# HMC5883L_Breakout-v11.net
KiCad netlist of a schematic drawn in EAGLE
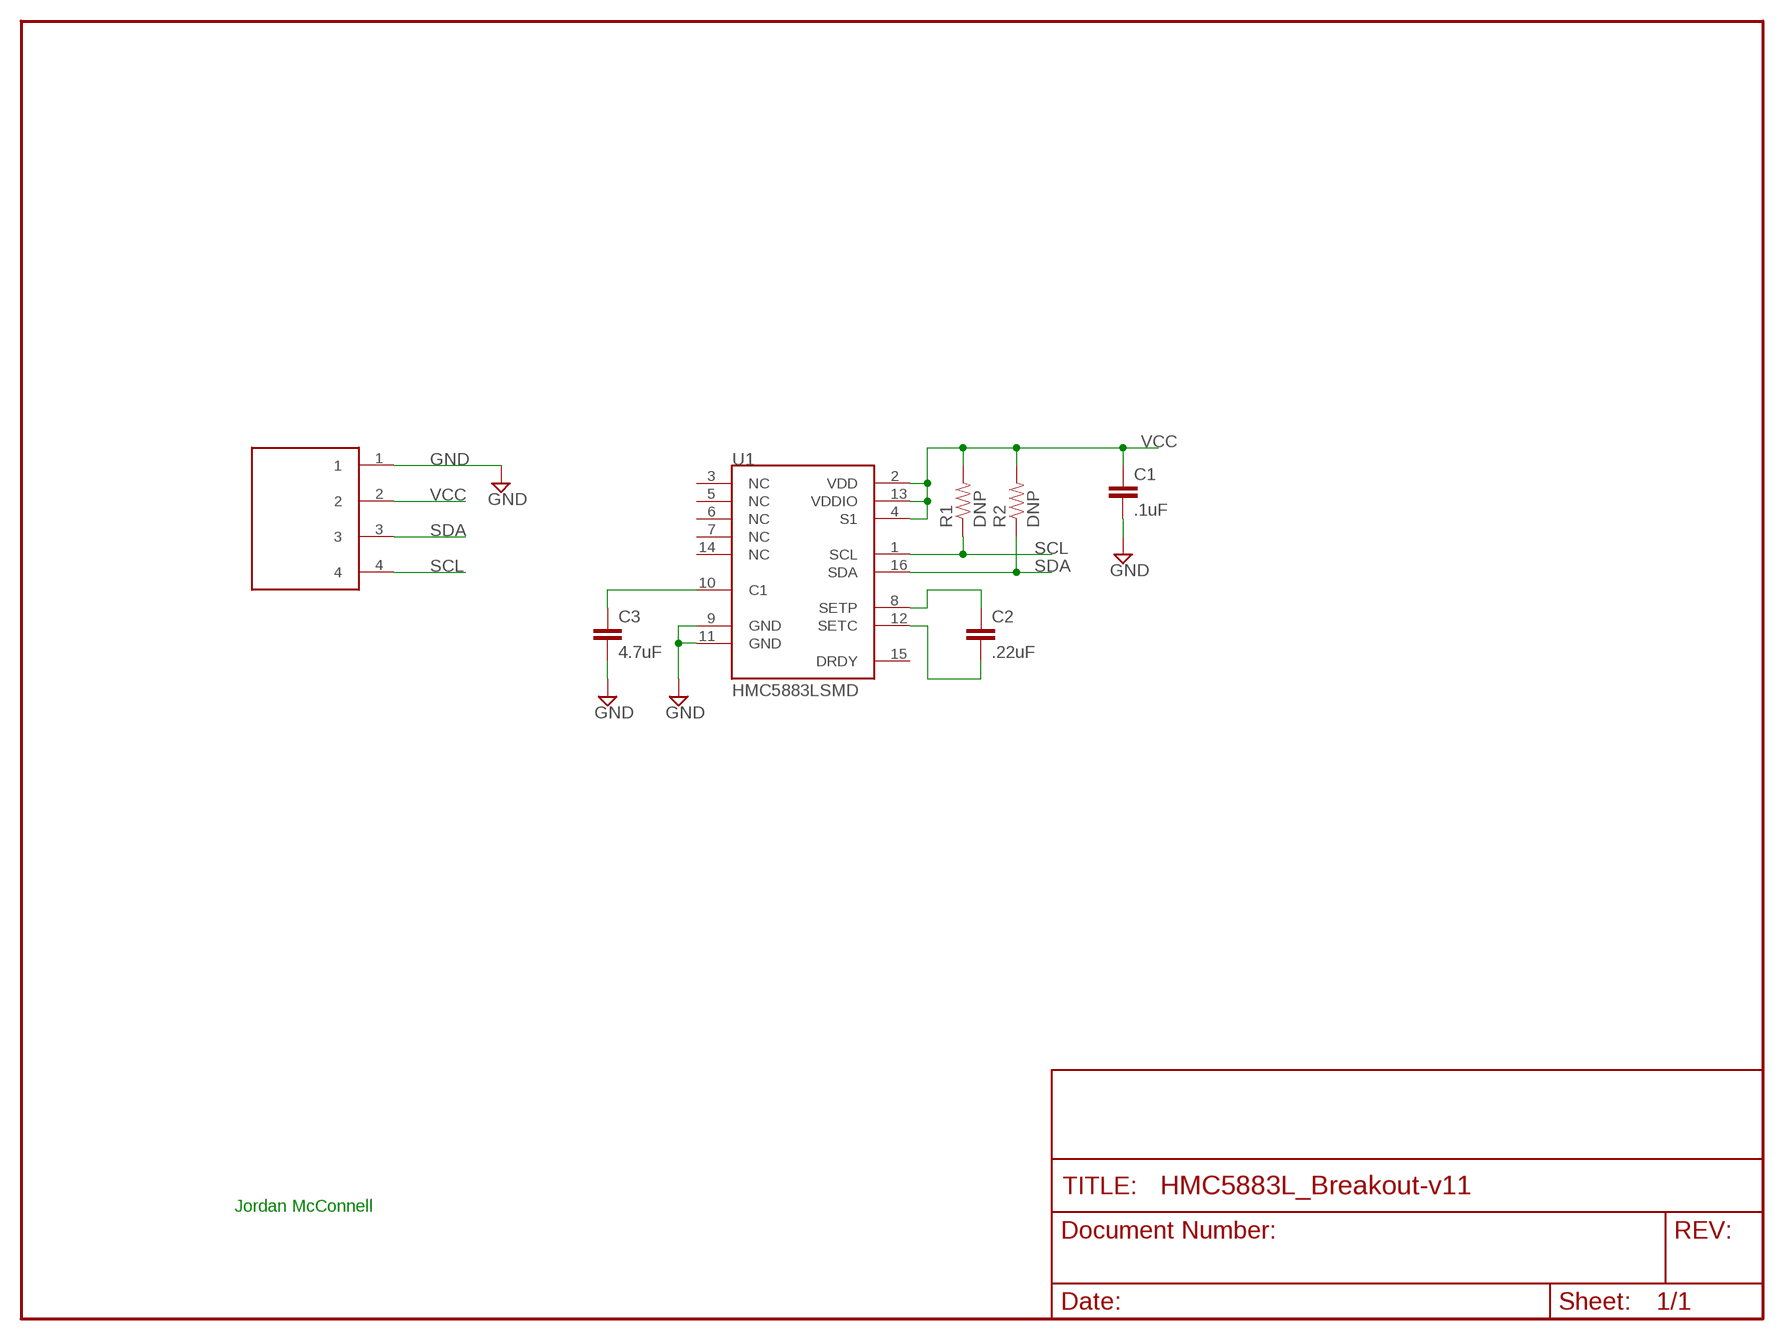
[diagram p0: schematic, sheet 1]

(export (version "E")
  (design (tool "Eeschema 10.0.6"))
  (components
    (comp (ref "C1")
      (value ".1uF")
      (footprint "eagle-import:0402-CAP")
      (libsource (lib "eagle-import") (part "CAP0402-CAP"))
    )
    (comp (ref "C2")
      (value ".22uF")
      (footprint "eagle-import:0402-CAP")
      (libsource (lib "eagle-import") (part "CAP0402-CAP"))
    )
    (comp (ref "C3")
      (value "4.7uF")
      (footprint "eagle-import:0402-CAP")
      (libsource (lib "eagle-import") (part "CAP0402-CAP"))
    )
    (comp (ref "JP1")
      (value "M80-879")
      (footprint "eagle-import:M80-879")
      (libsource (lib "eagle-import") (part "M80-879"))
    )
    (comp (ref "R1")
      (value "DNP")
      (footprint "eagle-import:0402-RES")
      (libsource (lib "eagle-import") (part "RESISTOR0402-RES"))
    )
    (comp (ref "R2")
      (value "DNP")
      (footprint "eagle-import:0402-RES")
      (libsource (lib "eagle-import") (part "RESISTOR0402-RES"))
    )
    (comp (ref "U1")
      (value "HMC5883LSMD")
      (footprint "eagle-import:16LPCC")
      (libsource (lib "eagle-import") (part "HMC5883LSMD"))
    )
  )
  (nets
    (net (code "1") (name "/SCL") (class "Default")
      (node (ref "JP1") (pin "4") (pinfunction "4_4") (pintype "bidirectional"))
      (node (ref "R1") (pin "1") (pinfunction "1_1") (pintype "passive"))
      (node (ref "U1") (pin "1") (pinfunction "SCL_1") (pintype "bidirectional"))
    )
    (net (code "2") (name "/SDA") (class "Default")
      (node (ref "JP1") (pin "3") (pinfunction "3_3") (pintype "bidirectional"))
      (node (ref "R2") (pin "1") (pinfunction "1_1") (pintype "passive"))
      (node (ref "U1") (pin "16") (pinfunction "SDA_16") (pintype "bidirectional"))
    )
    (net (code "3") (name "/VCC") (class "Default")
      (node (ref "C1") (pin "1") (pinfunction "1_1") (pintype "passive"))
      (node (ref "JP1") (pin "2") (pinfunction "2_2") (pintype "bidirectional"))
      (node (ref "R1") (pin "2") (pinfunction "2_2") (pintype "passive"))
      (node (ref "R2") (pin "2") (pinfunction "2_2") (pintype "passive"))
      (node (ref "U1") (pin "13") (pinfunction "VDDIO_13") (pintype "bidirectional"))
      (node (ref "U1") (pin "2") (pinfunction "VDD_2") (pintype "bidirectional"))
      (node (ref "U1") (pin "4") (pinfunction "S1_4") (pintype "bidirectional"))
    )
    (net (code "4") (name "GND") (class "Default")
      (node (ref "C1") (pin "2") (pinfunction "2_2") (pintype "passive"))
      (node (ref "C3") (pin "2") (pinfunction "2_2") (pintype "passive"))
      (node (ref "JP1") (pin "1") (pinfunction "1_1") (pintype "bidirectional"))
      (node (ref "U1") (pin "11") (pinfunction "GND_11") (pintype "bidirectional"))
      (node (ref "U1") (pin "9") (pinfunction "GND_9") (pintype "bidirectional"))
    )
    (net (code "5") (name "Net-(U1-C1)") (class "Default")
      (node (ref "C3") (pin "1") (pinfunction "1_1") (pintype "passive"))
      (node (ref "U1") (pin "10") (pinfunction "C1_10") (pintype "bidirectional"))
    )
    (net (code "6") (name "Net-(U1-SETC)") (class "Default")
      (node (ref "C2") (pin "2") (pinfunction "2_2") (pintype "passive"))
      (node (ref "U1") (pin "12") (pinfunction "SETC_12") (pintype "bidirectional"))
    )
    (net (code "7") (name "Net-(U1-SETP)") (class "Default")
      (node (ref "C2") (pin "1") (pinfunction "1_1") (pintype "passive"))
      (node (ref "U1") (pin "8") (pinfunction "SETP_8") (pintype "bidirectional"))
    )
    (net (code "8") (name "unconnected-(U1-DRDY-Pad15)") (class "Default")
      (node (ref "U1") (pin "15") (pinfunction "DRDY_15") (pintype "bidirectional"))
    )
    (net (code "9") (name "unconnected-(U1-NC-Pad3)") (class "Default")
      (node (ref "U1") (pin "3") (pinfunction "NC_3") (pintype "bidirectional"))
    )
    (net (code "10") (name "unconnected-(U1-NC-Pad5)") (class "Default")
      (node (ref "U1") (pin "5") (pinfunction "NC_5") (pintype "bidirectional"))
    )
    (net (code "11") (name "unconnected-(U1-NC-Pad6)") (class "Default")
      (node (ref "U1") (pin "6") (pinfunction "NC_6") (pintype "bidirectional"))
    )
    (net (code "12") (name "unconnected-(U1-NC-Pad7)") (class "Default")
      (node (ref "U1") (pin "7") (pinfunction "NC_7") (pintype "bidirectional"))
    )
    (net (code "13") (name "unconnected-(U1-NC-Pad14)") (class "Default")
      (node (ref "U1") (pin "14") (pinfunction "NC_14") (pintype "bidirectional"))
    )
  )
)
